# cpu.net
KiCad netlist of a schematic drawn in Altium Designer
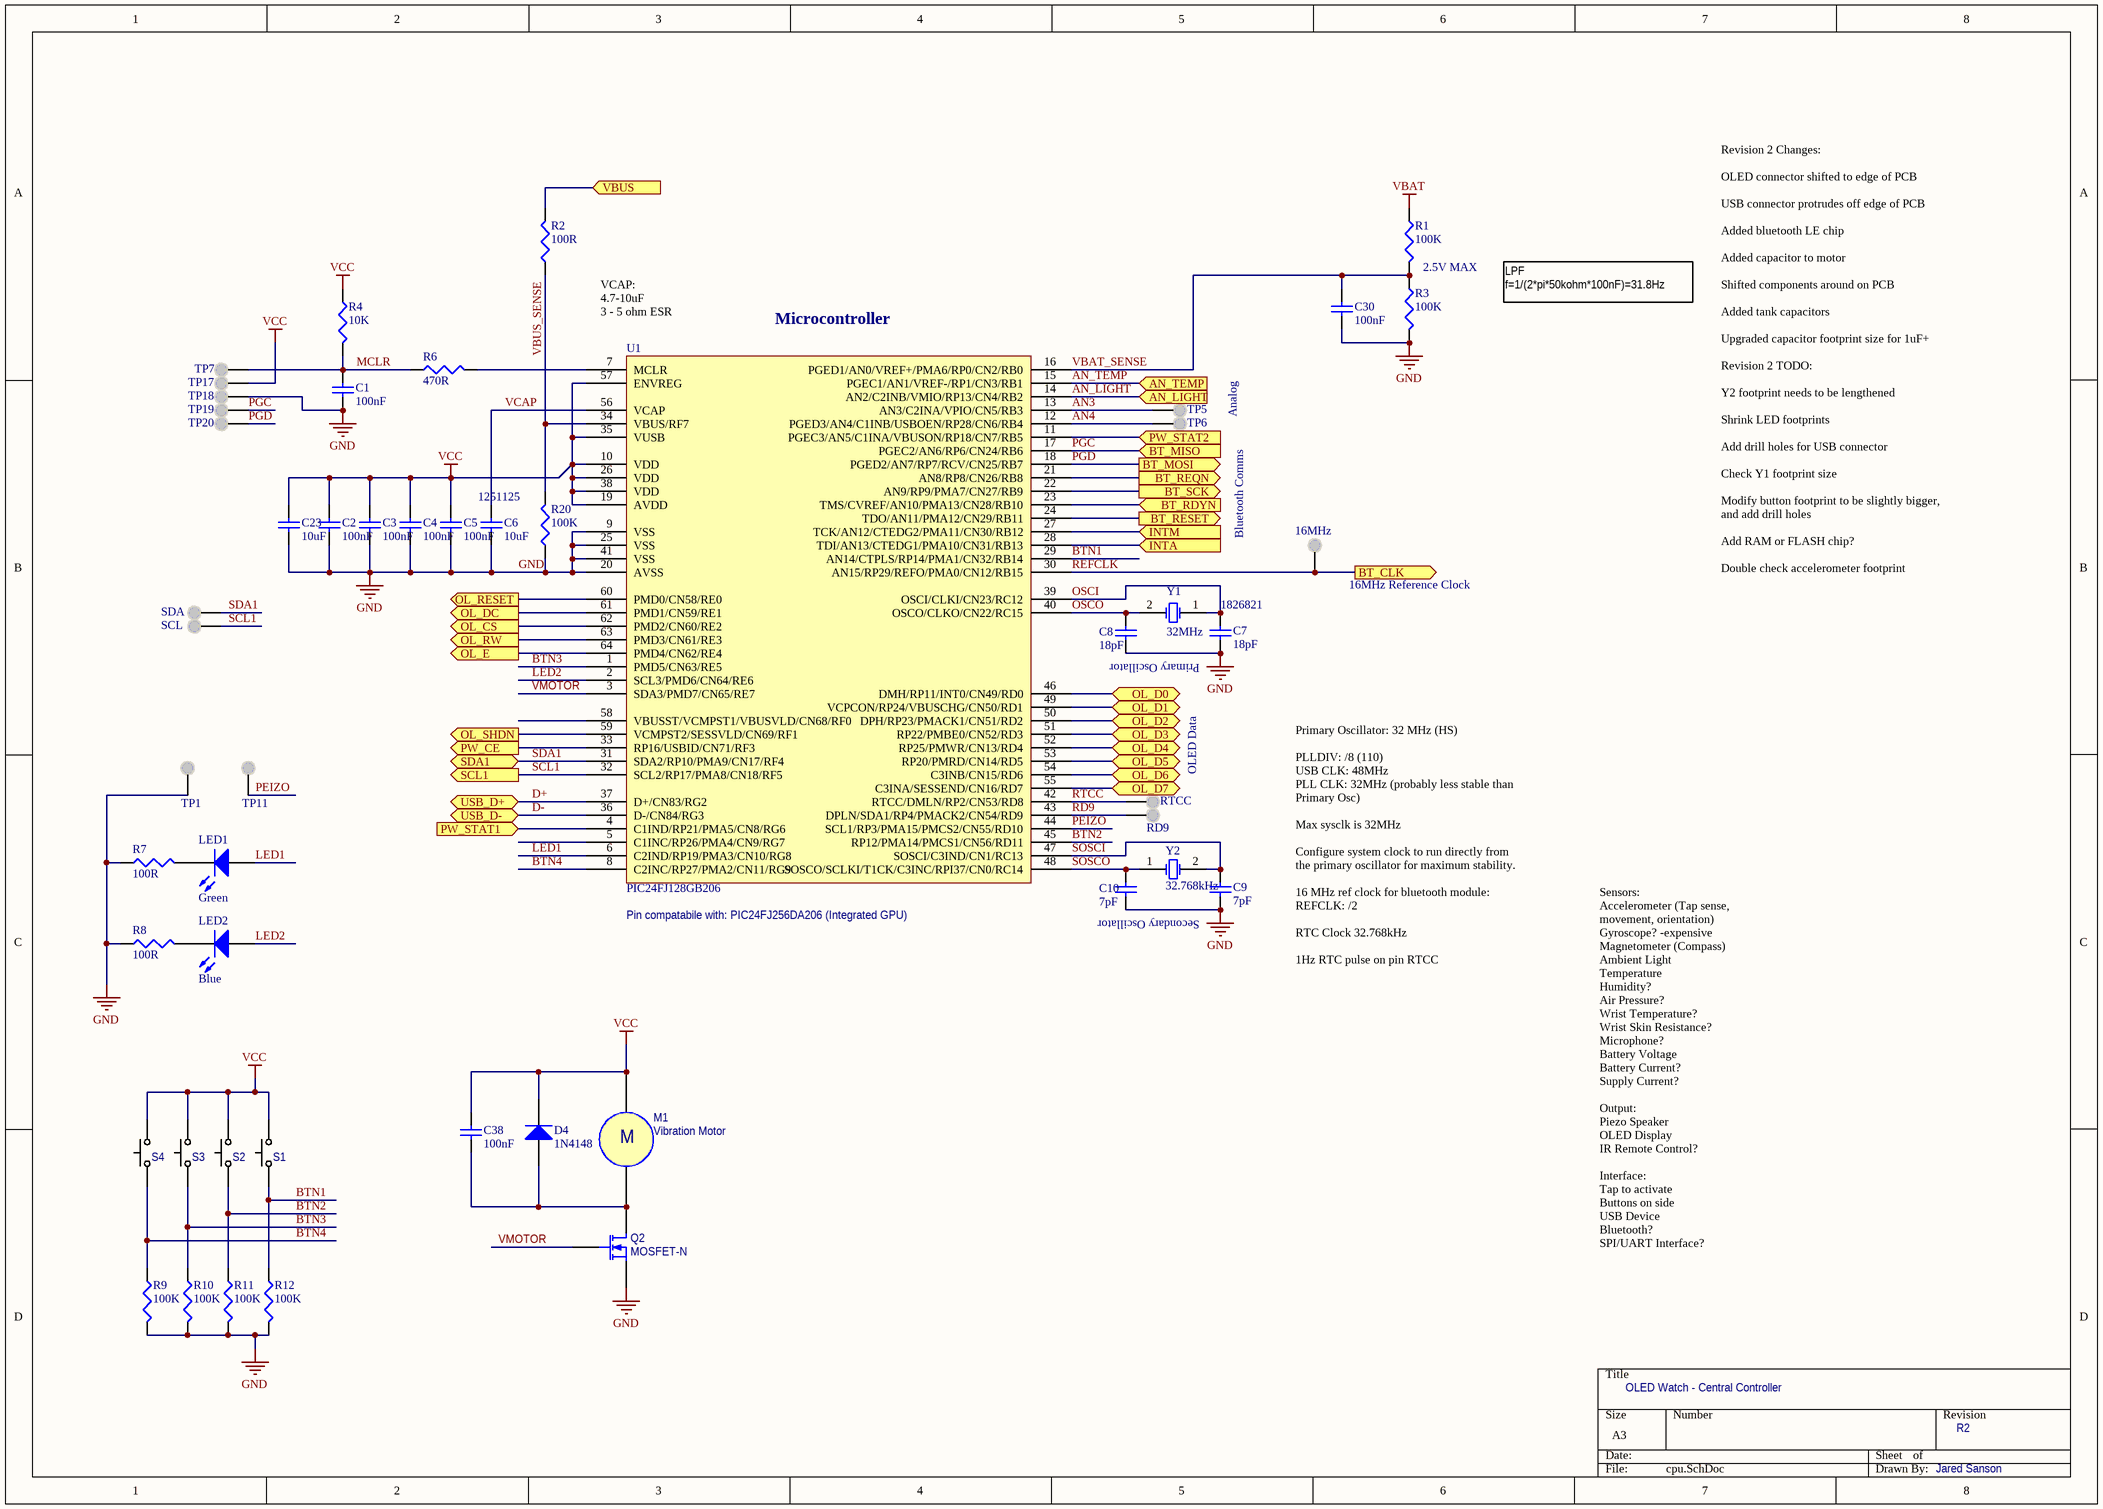
[diagram p0: cpu.SchDoc]

(export (version "E")
  (design (tool "Eeschema 10.0.6"))
  (components
    (comp (ref "C1")
      (value "100nF")
      (footprint "0603C")
      (description "Capacitor")
      (fields (field (name "Comment") "Cap") (field (name "PUBLISHER") "Altium Limited"))
      (libsource (lib "Miscellaneous Devices") (part "Cap"))
    )
    (comp (ref "C2")
      (value "100nF")
      (footprint "0603C")
      (description "Capacitor")
      (fields (field (name "Comment") "Cap") (field (name "PUBLISHER") "Altium Limited"))
      (libsource (lib "Miscellaneous Devices") (part "Cap"))
    )
    (comp (ref "C3")
      (value "100nF")
      (footprint "0603C")
      (description "Capacitor")
      (fields (field (name "Comment") "Cap") (field (name "PUBLISHER") "Altium Limited"))
      (libsource (lib "Miscellaneous Devices") (part "Cap"))
    )
    (comp (ref "C4")
      (value "100nF")
      (footprint "0603C")
      (description "Capacitor")
      (fields (field (name "Comment") "Cap") (field (name "PUBLISHER") "Altium Limited"))
      (libsource (lib "Miscellaneous Devices") (part "Cap"))
    )
    (comp (ref "C5")
      (value "100nF")
      (footprint "0603C")
      (description "Capacitor")
      (fields (field (name "Comment") "Cap") (field (name "PUBLISHER") "Altium Limited"))
      (libsource (lib "Miscellaneous Devices") (part "Cap"))
    )
    (comp (ref "C6")
      (value "10uF")
      (footprint "0805C")
      (description "Capacitor")
      (fields
        (field (name "SUPPLIER PART NUMBER 1") "1251125")
        (field (name "Comment") "Cap")
        (field (name "PUBLISHER") "Altium Limited")
      )
      (libsource (lib "Miscellaneous Devices") (part "Cap"))
    )
    (comp (ref "C7")
      (value "18pF")
      (footprint "0603C")
      (description "Capacitor")
      (fields (field (name "Comment") "Cap") (field (name "PUBLISHER") "Altium Limited"))
      (libsource (lib "Miscellaneous Devices") (part "Cap"))
    )
    (comp (ref "C8")
      (value "18pF")
      (footprint "0603C")
      (description "Capacitor")
      (fields (field (name "Comment") "Cap") (field (name "PUBLISHER") "Altium Limited"))
      (libsource (lib "Miscellaneous Devices") (part "Cap"))
    )
    (comp (ref "C9")
      (value "7pF")
      (footprint "0603C")
      (description "Capacitor")
      (fields (field (name "Comment") "Cap") (field (name "PUBLISHER") "Altium Limited"))
      (libsource (lib "Miscellaneous Devices") (part "Cap"))
    )
    (comp (ref "C10")
      (value "7pF")
      (footprint "0603C")
      (description "Capacitor")
      (fields (field (name "Comment") "Cap") (field (name "PUBLISHER") "Altium Limited"))
      (libsource (lib "Miscellaneous Devices") (part "Cap"))
    )
    (comp (ref "C23")
      (value "10uF")
      (footprint "0805C")
      (description "Capacitor")
      (fields (field (name "Comment") "Cap") (field (name "PUBLISHER") "Altium Limited"))
      (libsource (lib "Miscellaneous Devices") (part "Cap"))
    )
    (comp (ref "C30")
      (value "100nF")
      (footprint "0603C")
      (description "Capacitor")
      (fields (field (name "Comment") "Cap") (field (name "PUBLISHER") "Altium Limited"))
      (libsource (lib "Miscellaneous Devices") (part "Cap"))
    )
    (comp (ref "C38")
      (value "100nF")
      (footprint "0603C")
      (description "Capacitor")
      (fields (field (name "Comment") "Cap") (field (name "PUBLISHER") "Altium Limited"))
      (libsource (lib "Miscellaneous Devices") (part "Cap"))
    )
    (comp (ref "D4")
      (value "1N4148")
      (footprint "0603D")
      (description "Default Diode")
      (fields (field (name "PUBLISHER") "Altium Limited"))
      (libsource (lib "Miscellaneous Devices") (part "Diode"))
    )
    (comp (ref "LED1")
      (value "Green")
      (footprint "0603LED")
      (description "Typical RED, GREEN, YELLOW, AMBER GaAs LED")
      (fields (field (name "PUBLISHER") "Altium Limited"))
      (libsource (lib "Miscellaneous Devices") (part "LED2"))
    )
    (comp (ref "LED2")
      (value "Blue")
      (footprint "0603LED")
      (description "Typical RED, GREEN, YELLOW, AMBER GaAs LED")
      (fields (field (name "PUBLISHER") "Altium Limited"))
      (libsource (lib "Miscellaneous Devices") (part "LED2"))
    )
    (comp (ref "M1")
      (value "Vibration Motor")
      (footprint "VIBRATION_MOTOR")
      (libsource (lib "JLib") (part "VibrationMotor"))
    )
    (comp (ref "OSC")
      (value "16MHz")
      (footprint "TESTPOINT_TOP")
      (description "Test Point")
      (libsource (lib "JLib") (part "TestPoint"))
    )
    (comp (ref "Q2")
      (value "MOSFET-N")
      (footprint "SOT-23B_N")
      (description "N-Channel MOSFET")
      (fields (field (name "PUBLISHER") "Altium Limited"))
      (libsource (lib "Miscellaneous Devices") (part "MOSFET-N"))
    )
    (comp (ref "R1")
      (value "100K")
      (footprint "0603R")
      (description "Resistor")
      (fields (field (name "Comment") "Res3") (field (name "PUBLISHER") "Altium Limited"))
      (libsource (lib "Miscellaneous Devices") (part "Res3"))
    )
    (comp (ref "R2")
      (value "100R")
      (footprint "0603R")
      (description "Resistor")
      (fields (field (name "Comment") "Res3") (field (name "PUBLISHER") "Altium Limited"))
      (libsource (lib "Miscellaneous Devices") (part "Res3"))
    )
    (comp (ref "R3")
      (value "100K")
      (footprint "0603R")
      (description "Resistor")
      (fields (field (name "Comment") "Res3") (field (name "PUBLISHER") "Altium Limited"))
      (libsource (lib "Miscellaneous Devices") (part "Res3"))
    )
    (comp (ref "R4")
      (value "10K")
      (footprint "0603R")
      (description "Resistor")
      (fields (field (name "Comment") "Res3") (field (name "PUBLISHER") "Altium Limited"))
      (libsource (lib "Miscellaneous Devices") (part "Res3"))
    )
    (comp (ref "R6")
      (value "470R")
      (footprint "0603R")
      (description "Resistor")
      (fields (field (name "Comment") "Res3") (field (name "PUBLISHER") "Altium Limited"))
      (libsource (lib "Miscellaneous Devices") (part "Res3"))
    )
    (comp (ref "R7")
      (value "100R")
      (footprint "0603R")
      (description "Resistor")
      (fields (field (name "Comment") "Res3") (field (name "PUBLISHER") "Altium Limited"))
      (libsource (lib "Miscellaneous Devices") (part "Res3"))
    )
    (comp (ref "R8")
      (value "100R")
      (footprint "0603R")
      (description "Resistor")
      (fields (field (name "Comment") "Res3") (field (name "PUBLISHER") "Altium Limited"))
      (libsource (lib "Miscellaneous Devices") (part "Res3"))
    )
    (comp (ref "R9")
      (value "100K")
      (footprint "0603R")
      (description "Resistor")
      (fields (field (name "Comment") "Res3") (field (name "PUBLISHER") "Altium Limited"))
      (libsource (lib "Miscellaneous Devices") (part "Res3"))
    )
    (comp (ref "R10")
      (value "100K")
      (footprint "0603R")
      (description "Resistor")
      (fields (field (name "Comment") "Res3") (field (name "PUBLISHER") "Altium Limited"))
      (libsource (lib "Miscellaneous Devices") (part "Res3"))
    )
    (comp (ref "R11")
      (value "100K")
      (footprint "0603R")
      (description "Resistor")
      (fields (field (name "Comment") "Res3") (field (name "PUBLISHER") "Altium Limited"))
      (libsource (lib "Miscellaneous Devices") (part "Res3"))
    )
    (comp (ref "R12")
      (value "100K")
      (footprint "0603R")
      (description "Resistor")
      (fields (field (name "Comment") "Res3") (field (name "PUBLISHER") "Altium Limited"))
      (libsource (lib "Miscellaneous Devices") (part "Res3"))
    )
    (comp (ref "R20")
      (value "100K")
      (footprint "0603R")
      (description "Resistor")
      (fields (field (name "Comment") "Res3") (field (name "PUBLISHER") "Altium Limited"))
      (libsource (lib "Miscellaneous Devices") (part "Res3"))
    )
    (comp (ref "RD9")
      (value "~")
      (footprint "TESTPOINT_TOP")
      (description "Test Point")
      (libsource (lib "JLib") (part "TestPoint"))
    )
    (comp (ref "RTCC")
      (value "RTCC")
      (footprint "TESTPOINT_TOP")
      (description "Test Point")
      (libsource (lib "JLib") (part "TestPoint"))
    )
    (comp (ref "S1")
      (value "SideButton")
      (footprint "SIDE_BUTTON")
      (libsource (lib "JLib") (part "SideButton"))
    )
    (comp (ref "S2")
      (value "SideButton")
      (footprint "SIDE_BUTTON")
      (libsource (lib "JLib") (part "SideButton"))
    )
    (comp (ref "S3")
      (value "SideButton")
      (footprint "SIDE_BUTTON")
      (libsource (lib "JLib") (part "SideButton"))
    )
    (comp (ref "S4")
      (value "SideButton")
      (footprint "SIDE_BUTTON")
      (libsource (lib "JLib") (part "SideButton"))
    )
    (comp (ref "SCL")
      (value "SCL")
      (footprint "TESTPOINT_TOP")
      (description "Test Point")
      (libsource (lib "JLib") (part "TestPoint"))
    )
    (comp (ref "SDA")
      (value "SDA")
      (footprint "TESTPOINT_TOP")
      (description "Test Point")
      (libsource (lib "JLib") (part "TestPoint"))
    )
    (comp (ref "TP1")
      (value "PZ-")
      (footprint "TESTPOINT_TOP")
      (description "Test Point")
      (libsource (lib "JLib") (part "TestPoint"))
    )
    (comp (ref "TP5")
      (value "AN4")
      (footprint "TESTPOINT_TOP")
      (description "Test Point")
      (libsource (lib "JLib") (part "TestPoint"))
    )
    (comp (ref "TP6")
      (value "AN5")
      (footprint "TESTPOINT_TOP")
      (description "Test Point")
      (libsource (lib "JLib") (part "TestPoint"))
    )
    (comp (ref "TP7")
      (value "MCLR")
      (footprint "TESTPOINT_TOP")
      (description "Test Point")
      (libsource (lib "JLib") (part "TestPoint"))
    )
    (comp (ref "TP11")
      (value "PZ+")
      (footprint "TESTPOINT_TOP")
      (description "Test Point")
      (libsource (lib "JLib") (part "TestPoint"))
    )
    (comp (ref "TP17")
      (value "VCC")
      (footprint "TESTPOINT_TOP")
      (description "Test Point")
      (libsource (lib "JLib") (part "TestPoint"))
    )
    (comp (ref "TP18")
      (value "GND")
      (footprint "TESTPOINT_TOP")
      (description "Test Point")
      (libsource (lib "JLib") (part "TestPoint"))
    )
    (comp (ref "TP19")
      (value "PGC")
      (footprint "TESTPOINT_TOP")
      (description "Test Point")
      (libsource (lib "JLib") (part "TestPoint"))
    )
    (comp (ref "TP20")
      (value "PGD")
      (footprint "TESTPOINT_TOP")
      (description "Test Point")
      (libsource (lib "JLib") (part "TestPoint"))
    )
    (comp (ref "U1")
      (value "PIC24FJ128GB206")
      (footprint "TQFP_64_10MM")
      (libsource (lib "JLib") (part "PIC24FJ128GB206"))
    )
    (comp (ref "Y1")
      (value "32MHz")
      (footprint "ABRACON32MHZ")
      (description "Crystal Oscillator")
      (fields
        (field (name "SUPPLIER PART NUMBER 1") "1826821")
        (field (name "MANUFACTURER") "ABRACON")
        (field (name "MANUFACTURER PART NUMBER") "ABM3-32.000MHZ-D2Y-T")
        (field (name "PUBLISHER") "Altium Limited")
      )
      (libsource (lib "Miscellaneous Devices") (part "XTAL"))
    )
    (comp (ref "Y2")
      (value "32.768kHz")
      (footprint "BCY-W2/D1.5")
      (description "Crystal Oscillator")
      (fields (field (name "PUBLISHER") "Altium Limited"))
      (libsource (lib "Miscellaneous Devices") (part "XTAL"))
    )
  )
  (nets
    (net (code "1") (name "/AN3") (class "Default")
      (node (ref "TP5") (pin "1") (pinfunction "TP_1") (pintype "passive"))
      (node (ref "U1") (pin "13") (pinfunction "AN3/C2INA/VPIO/CN5/RB3_13") (pintype "passive"))
    )
    (net (code "2") (name "/AN4") (class "Default")
      (node (ref "TP6") (pin "1") (pinfunction "TP_1") (pintype "passive"))
      (node (ref "U1") (pin "12") (pinfunction "PGED3/AN4/C1INB/USBOEN/RP28/CN6/RB4_12") (pintype "passive"))
    )
    (net (code "3") (name "/AN_LIGHT") (class "Default")
      (node (ref "U1") (pin "14") (pinfunction "AN2/C2INB/VMIO/RP13/CN4/RB2_14") (pintype "passive"))
    )
    (net (code "4") (name "/AN_TEMP") (class "Default")
      (node (ref "U1") (pin "15") (pinfunction "PGEC1/AN1/VREF-/RP1/CN3/RB1_15") (pintype "passive"))
    )
    (net (code "5") (name "/BTN1") (class "Default")
      (node (ref "R12") (pin "1") (pinfunction "1_1") (pintype "passive"))
      (node (ref "S1") (pin "1") (pinfunction "1_1") (pintype "passive"))
      (node (ref "U1") (pin "29") (pinfunction "AN14/CTPLS/RP14/PMA1/CN32/RB14_29") (pintype "passive"))
    )
    (net (code "6") (name "/BTN2") (class "Default")
      (node (ref "R11") (pin "1") (pinfunction "1_1") (pintype "passive"))
      (node (ref "S2") (pin "1") (pinfunction "1_1") (pintype "passive"))
      (node (ref "U1") (pin "45") (pinfunction "RP12/PMA14/PMCS1/CN56/RD11_45") (pintype "passive"))
    )
    (net (code "7") (name "/BTN3") (class "Default")
      (node (ref "R10") (pin "1") (pinfunction "1_1") (pintype "passive"))
      (node (ref "S3") (pin "1") (pinfunction "1_1") (pintype "passive"))
      (node (ref "U1") (pin "1") (pinfunction "PMD5/CN63/RE5_1") (pintype "passive"))
    )
    (net (code "8") (name "/BTN4") (class "Default")
      (node (ref "R9") (pin "1") (pinfunction "1_1") (pintype "passive"))
      (node (ref "S4") (pin "1") (pinfunction "1_1") (pintype "passive"))
      (node (ref "U1") (pin "8") (pinfunction "C2INC/RP27/PMA2/CN11/RG9_8") (pintype "passive"))
    )
    (net (code "9") (name "/BT_RDYN") (class "Default")
      (node (ref "U1") (pin "23") (pinfunction "TMS/CVREF/AN10/PMA13/CN28/RB10_23") (pintype "passive"))
    )
    (net (code "10") (name "/BT_REQN") (class "Default")
      (node (ref "U1") (pin "21") (pinfunction "AN8/RP8/CN26/RB8_21") (pintype "passive"))
    )
    (net (code "11") (name "/BT_RESET") (class "Default")
      (node (ref "U1") (pin "24") (pinfunction "TDO/AN11/PMA12/CN29/RB11_24") (pintype "passive"))
    )
    (net (code "12") (name "/BT_SCK") (class "Default")
      (node (ref "U1") (pin "22") (pinfunction "AN9/RP9/PMA7/CN27/RB9_22") (pintype "passive"))
    )
    (net (code "13") (name "/D+") (class "Default")
      (node (ref "U1") (pin "37") (pinfunction "D+/CN83/RG2_37") (pintype "passive"))
    )
    (net (code "14") (name "/D-") (class "Default")
      (node (ref "U1") (pin "36") (pinfunction "D-/CN84/RG3_36") (pintype "passive"))
    )
    (net (code "15") (name "/INTA") (class "Default")
      (node (ref "U1") (pin "28") (pinfunction "TDI/AN13/CTEDG1/PMA10/CN31/RB13_28") (pintype "passive"))
    )
    (net (code "16") (name "/INTM") (class "Default")
      (node (ref "U1") (pin "27") (pinfunction "TCK/AN12/CTEDG2/PMA11/CN30/RB12_27") (pintype "passive"))
    )
    (net (code "17") (name "/LED1") (class "Default")
      (node (ref "LED1") (pin "1") (pinfunction "A_1") (pintype "passive"))
      (node (ref "U1") (pin "6") (pinfunction "C2IND/RP19/PMA3/CN10/RG8_6") (pintype "passive"))
    )
    (net (code "18") (name "/LED2") (class "Default")
      (node (ref "LED2") (pin "1") (pinfunction "A_1") (pintype "passive"))
      (node (ref "U1") (pin "2") (pinfunction "SCL3/PMD6/CN64/RE6_2") (pintype "passive"))
    )
    (net (code "19") (name "/MCLR") (class "Default")
      (node (ref "C1") (pin "1") (pinfunction "1_1") (pintype "passive"))
      (node (ref "R4") (pin "2") (pinfunction "2_2") (pintype "passive"))
      (node (ref "R6") (pin "1") (pinfunction "1_1") (pintype "passive"))
      (node (ref "TP7") (pin "1") (pinfunction "TP_1") (pintype "passive"))
    )
    (net (code "20") (name "/OL_CS") (class "Default")
      (node (ref "U1") (pin "62") (pinfunction "PMD2/CN60/RE2_62") (pintype "passive"))
    )
    (net (code "21") (name "/OL_D0") (class "Default")
      (node (ref "U1") (pin "46") (pinfunction "DMH/RP11/INT0/CN49/RD0_46") (pintype "passive"))
    )
    (net (code "22") (name "/OL_D1") (class "Default")
      (node (ref "U1") (pin "49") (pinfunction "VCPCON/RP24/VBUSCHG/CN50/RD1_49") (pintype "passive"))
    )
    (net (code "23") (name "/OL_D2") (class "Default")
      (node (ref "U1") (pin "50") (pinfunction "DPH/RP23/PMACK1/CN51/RD2_50") (pintype "passive"))
    )
    (net (code "24") (name "/OL_D3") (class "Default")
      (node (ref "U1") (pin "51") (pinfunction "RP22/PMBE0/CN52/RD3_51") (pintype "passive"))
    )
    (net (code "25") (name "/OL_D4") (class "Default")
      (node (ref "U1") (pin "52") (pinfunction "RP25/PMWR/CN13/RD4_52") (pintype "passive"))
    )
    (net (code "26") (name "/OL_D5") (class "Default")
      (node (ref "U1") (pin "53") (pinfunction "RP20/PMRD/CN14/RD5_53") (pintype "passive"))
    )
    (net (code "27") (name "/OL_D6") (class "Default")
      (node (ref "U1") (pin "54") (pinfunction "C3INB/CN15/RD6_54") (pintype "passive"))
    )
    (net (code "28") (name "/OL_D7") (class "Default")
      (node (ref "U1") (pin "55") (pinfunction "C3INA/SESSEND/CN16/RD7_55") (pintype "passive"))
    )
    (net (code "29") (name "/OL_DC") (class "Default")
      (node (ref "U1") (pin "61") (pinfunction "PMD1/CN59/RE1_61") (pintype "passive"))
    )
    (net (code "30") (name "/OL_E") (class "Default")
      (node (ref "U1") (pin "64") (pinfunction "PMD4/CN62/RE4_64") (pintype "passive"))
    )
    (net (code "31") (name "/OL_RESET") (class "Default")
      (node (ref "U1") (pin "60") (pinfunction "PMD0/CN58/RE0_60") (pintype "passive"))
    )
    (net (code "32") (name "/OL_RW") (class "Default")
      (node (ref "U1") (pin "63") (pinfunction "PMD3/CN61/RE3_63") (pintype "passive"))
    )
    (net (code "33") (name "/OL_SHDN") (class "Default")
      (node (ref "U1") (pin "59") (pinfunction "VCMPST2/SESSVLD/CN69/RF1_59") (pintype "passive"))
    )
    (net (code "34") (name "/OSCI") (class "Default")
      (node (ref "C7") (pin "1") (pinfunction "1_1") (pintype "passive"))
      (node (ref "U1") (pin "39") (pinfunction "OSCI/CLKI/CN23/RC12_39") (pintype "passive"))
      (node (ref "Y1") (pin "1") (pinfunction "OSC1_1") (pintype "passive"))
    )
    (net (code "35") (name "/OSCO") (class "Default")
      (node (ref "C8") (pin "1") (pinfunction "1_1") (pintype "passive"))
      (node (ref "U1") (pin "40") (pinfunction "OSCO/CLKO/CN22/RC15_40") (pintype "passive"))
      (node (ref "Y1") (pin "2") (pinfunction "OSC2_2") (pintype "passive"))
    )
    (net (code "36") (name "/PEIZO") (class "Default")
      (node (ref "TP11") (pin "1") (pinfunction "TP_1") (pintype "passive"))
      (node (ref "U1") (pin "44") (pinfunction "SCL1/RP3/PMA15/PMCS2/CN55/RD10_44") (pintype "passive"))
    )
    (net (code "37") (name "/PGC") (class "Default")
      (node (ref "TP19") (pin "1") (pinfunction "TP_1") (pintype "passive"))
      (node (ref "U1") (pin "17") (pinfunction "PGEC2/AN6/RP6/CN24/RB6_17") (pintype "passive"))
    )
    (net (code "38") (name "/PGD") (class "Default")
      (node (ref "TP20") (pin "1") (pinfunction "TP_1") (pintype "passive"))
      (node (ref "U1") (pin "18") (pinfunction "PGED2/AN7/RP7/RCV/CN25/RB7_18") (pintype "passive"))
    )
    (net (code "39") (name "/PW_CE") (class "Default")
      (node (ref "U1") (pin "33") (pinfunction "RP16/USBID/CN71/RF3_33") (pintype "passive"))
    )
    (net (code "40") (name "/PW_STAT1") (class "Default")
      (node (ref "U1") (pin "4") (pinfunction "C1IND/RP21/PMA5/CN8/RG6_4") (pintype "passive"))
    )
    (net (code "41") (name "/PW_STAT2") (class "Default")
      (node (ref "U1") (pin "11") (pinfunction "PGEC3/AN5/C1INA/VBUSON/RP18/CN7/RB5_11") (pintype "passive"))
    )
    (net (code "42") (name "/RD9") (class "Default")
      (node (ref "RD9") (pin "1") (pinfunction "TP_1") (pintype "passive"))
      (node (ref "U1") (pin "43") (pinfunction "DPLN/SDA1/RP4/PMACK2/CN54/RD9_43") (pintype "passive"))
    )
    (net (code "43") (name "/REFCLK") (class "Default")
      (node (ref "OSC") (pin "1") (pinfunction "TP_1") (pintype "passive"))
      (node (ref "U1") (pin "30") (pinfunction "AN15/RP29/REFO/PMA0/CN12/RB15_30") (pintype "passive"))
    )
    (net (code "44") (name "/RTCC") (class "Default")
      (node (ref "RTCC") (pin "1") (pinfunction "TP_1") (pintype "passive"))
      (node (ref "U1") (pin "42") (pinfunction "RTCC/DMLN/RP2/CN53/RD8_42") (pintype "passive"))
    )
    (net (code "45") (name "/SCL1") (class "Default")
      (node (ref "SCL") (pin "1") (pinfunction "TP_1") (pintype "passive"))
      (node (ref "U1") (pin "32") (pinfunction "SCL2/RP17/PMA8/CN18/RF5_32") (pintype "passive"))
    )
    (net (code "46") (name "/SDA1") (class "Default")
      (node (ref "SDA") (pin "1") (pinfunction "TP_1") (pintype "passive"))
      (node (ref "U1") (pin "31") (pinfunction "SDA2/RP10/PMA9/CN17/RF4_31") (pintype "passive"))
    )
    (net (code "47") (name "/SOSCI") (class "Default")
      (node (ref "C9") (pin "1") (pinfunction "1_1") (pintype "passive"))
      (node (ref "U1") (pin "47") (pinfunction "SOSCI/C3IND/CN1/RC13_47") (pintype "passive"))
      (node (ref "Y2") (pin "2") (pinfunction "OSC2_2") (pintype "passive"))
    )
    (net (code "48") (name "/SOSCO") (class "Default")
      (node (ref "C10") (pin "1") (pinfunction "1_1") (pintype "passive"))
      (node (ref "U1") (pin "48") (pinfunction "SOSCO/SCLKI/T1CK/C3INC/RPI37/CN0/RC14_48") (pintype "passive"))
      (node (ref "Y2") (pin "1") (pinfunction "OSC1_1") (pintype "passive"))
    )
    (net (code "49") (name "/VBAT_SENSE") (class "Default")
      (node (ref "C30") (pin "1") (pinfunction "1_1") (pintype "passive"))
      (node (ref "R1") (pin "2") (pinfunction "2_2") (pintype "passive"))
      (node (ref "R3") (pin "1") (pinfunction "1_1") (pintype "passive"))
      (node (ref "U1") (pin "16") (pinfunction "PGED1/AN0/VREF+/PMA6/RP0/CN2/RB0_16") (pintype "passive"))
    )
    (net (code "50") (name "/VBUS") (class "Default")
      (node (ref "R2") (pin "2") (pinfunction "2_2") (pintype "passive"))
    )
    (net (code "51") (name "/VBUS_SENSE") (class "Default")
      (node (ref "R2") (pin "1") (pinfunction "1_1") (pintype "passive"))
      (node (ref "R20") (pin "2") (pinfunction "2_2") (pintype "passive"))
      (node (ref "U1") (pin "34") (pinfunction "VBUS/RF7_34") (pintype "passive"))
    )
    (net (code "52") (name "/VCAP") (class "Default")
      (node (ref "C6") (pin "1") (pinfunction "1_1") (pintype "passive"))
      (node (ref "U1") (pin "56") (pinfunction "VCAP_56") (pintype "passive"))
    )
    (net (code "53") (name "/VMOTOR") (class "Default")
      (node (ref "Q2") (pin "2") (pinfunction "G_2") (pintype "passive"))
      (node (ref "U1") (pin "3") (pinfunction "SDA3/PMD7/CN65/RE7_3") (pintype "passive"))
    )
    (net (code "54") (name "GND") (class "Default")
      (node (ref "C1") (pin "2") (pinfunction "2_2") (pintype "passive"))
      (node (ref "C10") (pin "2") (pinfunction "2_2") (pintype "passive"))
      (node (ref "C2") (pin "2") (pinfunction "2_2") (pintype "passive"))
      (node (ref "C23") (pin "2") (pinfunction "2_2") (pintype "passive"))
      (node (ref "C3") (pin "2") (pinfunction "2_2") (pintype "passive"))
      (node (ref "C30") (pin "2") (pinfunction "2_2") (pintype "passive"))
      (node (ref "C4") (pin "2") (pinfunction "2_2") (pintype "passive"))
      (node (ref "C5") (pin "2") (pinfunction "2_2") (pintype "passive"))
      (node (ref "C6") (pin "2") (pinfunction "2_2") (pintype "passive"))
      (node (ref "C7") (pin "2") (pinfunction "2_2") (pintype "passive"))
      (node (ref "C8") (pin "2") (pinfunction "2_2") (pintype "passive"))
      (node (ref "C9") (pin "2") (pinfunction "2_2") (pintype "passive"))
      (node (ref "Q2") (pin "3") (pinfunction "S_3") (pintype "passive"))
      (node (ref "R10") (pin "2") (pinfunction "2_2") (pintype "passive"))
      (node (ref "R11") (pin "2") (pinfunction "2_2") (pintype "passive"))
      (node (ref "R12") (pin "2") (pinfunction "2_2") (pintype "passive"))
      (node (ref "R20") (pin "1") (pinfunction "1_1") (pintype "passive"))
      (node (ref "R3") (pin "2") (pinfunction "2_2") (pintype "passive"))
      (node (ref "R7") (pin "1") (pinfunction "1_1") (pintype "passive"))
      (node (ref "R8") (pin "1") (pinfunction "1_1") (pintype "passive"))
      (node (ref "R9") (pin "2") (pinfunction "2_2") (pintype "passive"))
      (node (ref "TP1") (pin "1") (pinfunction "TP_1") (pintype "passive"))
      (node (ref "TP18") (pin "1") (pinfunction "TP_1") (pintype "passive"))
      (node (ref "U1") (pin "20") (pinfunction "AVSS_20") (pintype "passive"))
      (node (ref "U1") (pin "25") (pinfunction "VSS_25") (pintype "passive"))
      (node (ref "U1") (pin "41") (pinfunction "VSS_41") (pintype "passive"))
      (node (ref "U1") (pin "9") (pinfunction "VSS_9") (pintype "passive"))
    )
    (net (code "55") (name "Net-(D4-A)") (class "Default")
      (node (ref "C38") (pin "2") (pinfunction "2_2") (pintype "passive"))
      (node (ref "D4") (pin "1") (pinfunction "A_1") (pintype "passive"))
      (node (ref "M1") (pin "2") (pinfunction "2_2") (pintype "passive"))
      (node (ref "Q2") (pin "1") (pinfunction "D_1") (pintype "passive"))
    )
    (net (code "56") (name "Net-(LED1-K)") (class "Default")
      (node (ref "LED1") (pin "2") (pinfunction "K_2") (pintype "passive"))
      (node (ref "R7") (pin "2") (pinfunction "2_2") (pintype "passive"))
    )
    (net (code "57") (name "Net-(LED2-K)") (class "Default")
      (node (ref "LED2") (pin "2") (pinfunction "K_2") (pintype "passive"))
      (node (ref "R8") (pin "2") (pinfunction "2_2") (pintype "passive"))
    )
    (net (code "58") (name "Net-(U1-MCLR)") (class "Default")
      (node (ref "R6") (pin "2") (pinfunction "2_2") (pintype "passive"))
      (node (ref "U1") (pin "7") (pinfunction "MCLR_7") (pintype "passive"))
    )
    (net (code "59") (name "VBAT") (class "Default")
      (node (ref "R1") (pin "1") (pinfunction "1_1") (pintype "passive"))
    )
    (net (code "60") (name "VCC") (class "Default")
      (node (ref "C2") (pin "1") (pinfunction "1_1") (pintype "passive"))
      (node (ref "C23") (pin "1") (pinfunction "1_1") (pintype "passive"))
      (node (ref "C3") (pin "1") (pinfunction "1_1") (pintype "passive"))
      (node (ref "C38") (pin "1") (pinfunction "1_1") (pintype "passive"))
      (node (ref "C4") (pin "1") (pinfunction "1_1") (pintype "passive"))
      (node (ref "C5") (pin "1") (pinfunction "1_1") (pintype "passive"))
      (node (ref "D4") (pin "2") (pinfunction "K_2") (pintype "passive"))
      (node (ref "M1") (pin "1") (pinfunction "1_1") (pintype "passive"))
      (node (ref "R4") (pin "1") (pinfunction "1_1") (pintype "passive"))
      (node (ref "S1") (pin "2") (pinfunction "2_2") (pintype "passive"))
      (node (ref "S2") (pin "2") (pinfunction "2_2") (pintype "passive"))
      (node (ref "S3") (pin "2") (pinfunction "2_2") (pintype "passive"))
      (node (ref "S4") (pin "2") (pinfunction "2_2") (pintype "passive"))
      (node (ref "TP17") (pin "1") (pinfunction "TP_1") (pintype "passive"))
      (node (ref "U1") (pin "10") (pinfunction "VDD_10") (pintype "passive"))
      (node (ref "U1") (pin "19") (pinfunction "AVDD_19") (pintype "passive"))
      (node (ref "U1") (pin "26") (pinfunction "VDD_26") (pintype "passive"))
      (node (ref "U1") (pin "35") (pinfunction "VUSB_35") (pintype "passive"))
      (node (ref "U1") (pin "38") (pinfunction "VDD_38") (pintype "passive"))
      (node (ref "U1") (pin "57") (pinfunction "ENVREG_57") (pintype "passive"))
    )
    (net (code "61") (name "unconnected-(U1-C1INC{slash}RP26{slash}PMA4{slash}CN9{slash}RG7-Pad5)") (class "Default")
      (node (ref "U1") (pin "5") (pinfunction "C1INC/RP26/PMA4/CN9/RG7_5") (pintype "passive"))
    )
    (net (code "62") (name "unconnected-(U1-VBUSST{slash}VCMPST1{slash}VBUSVLD{slash}CN68{slash}RF0-Pad58)") (class "Default")
      (node (ref "U1") (pin "58") (pinfunction "VBUSST/VCMPST1/VBUSVLD/CN68/RF0_58") (pintype "passive"))
    )
  )
)
